# Sheet1.net
KiCad netlist of a schematic drawn in Altium Designer
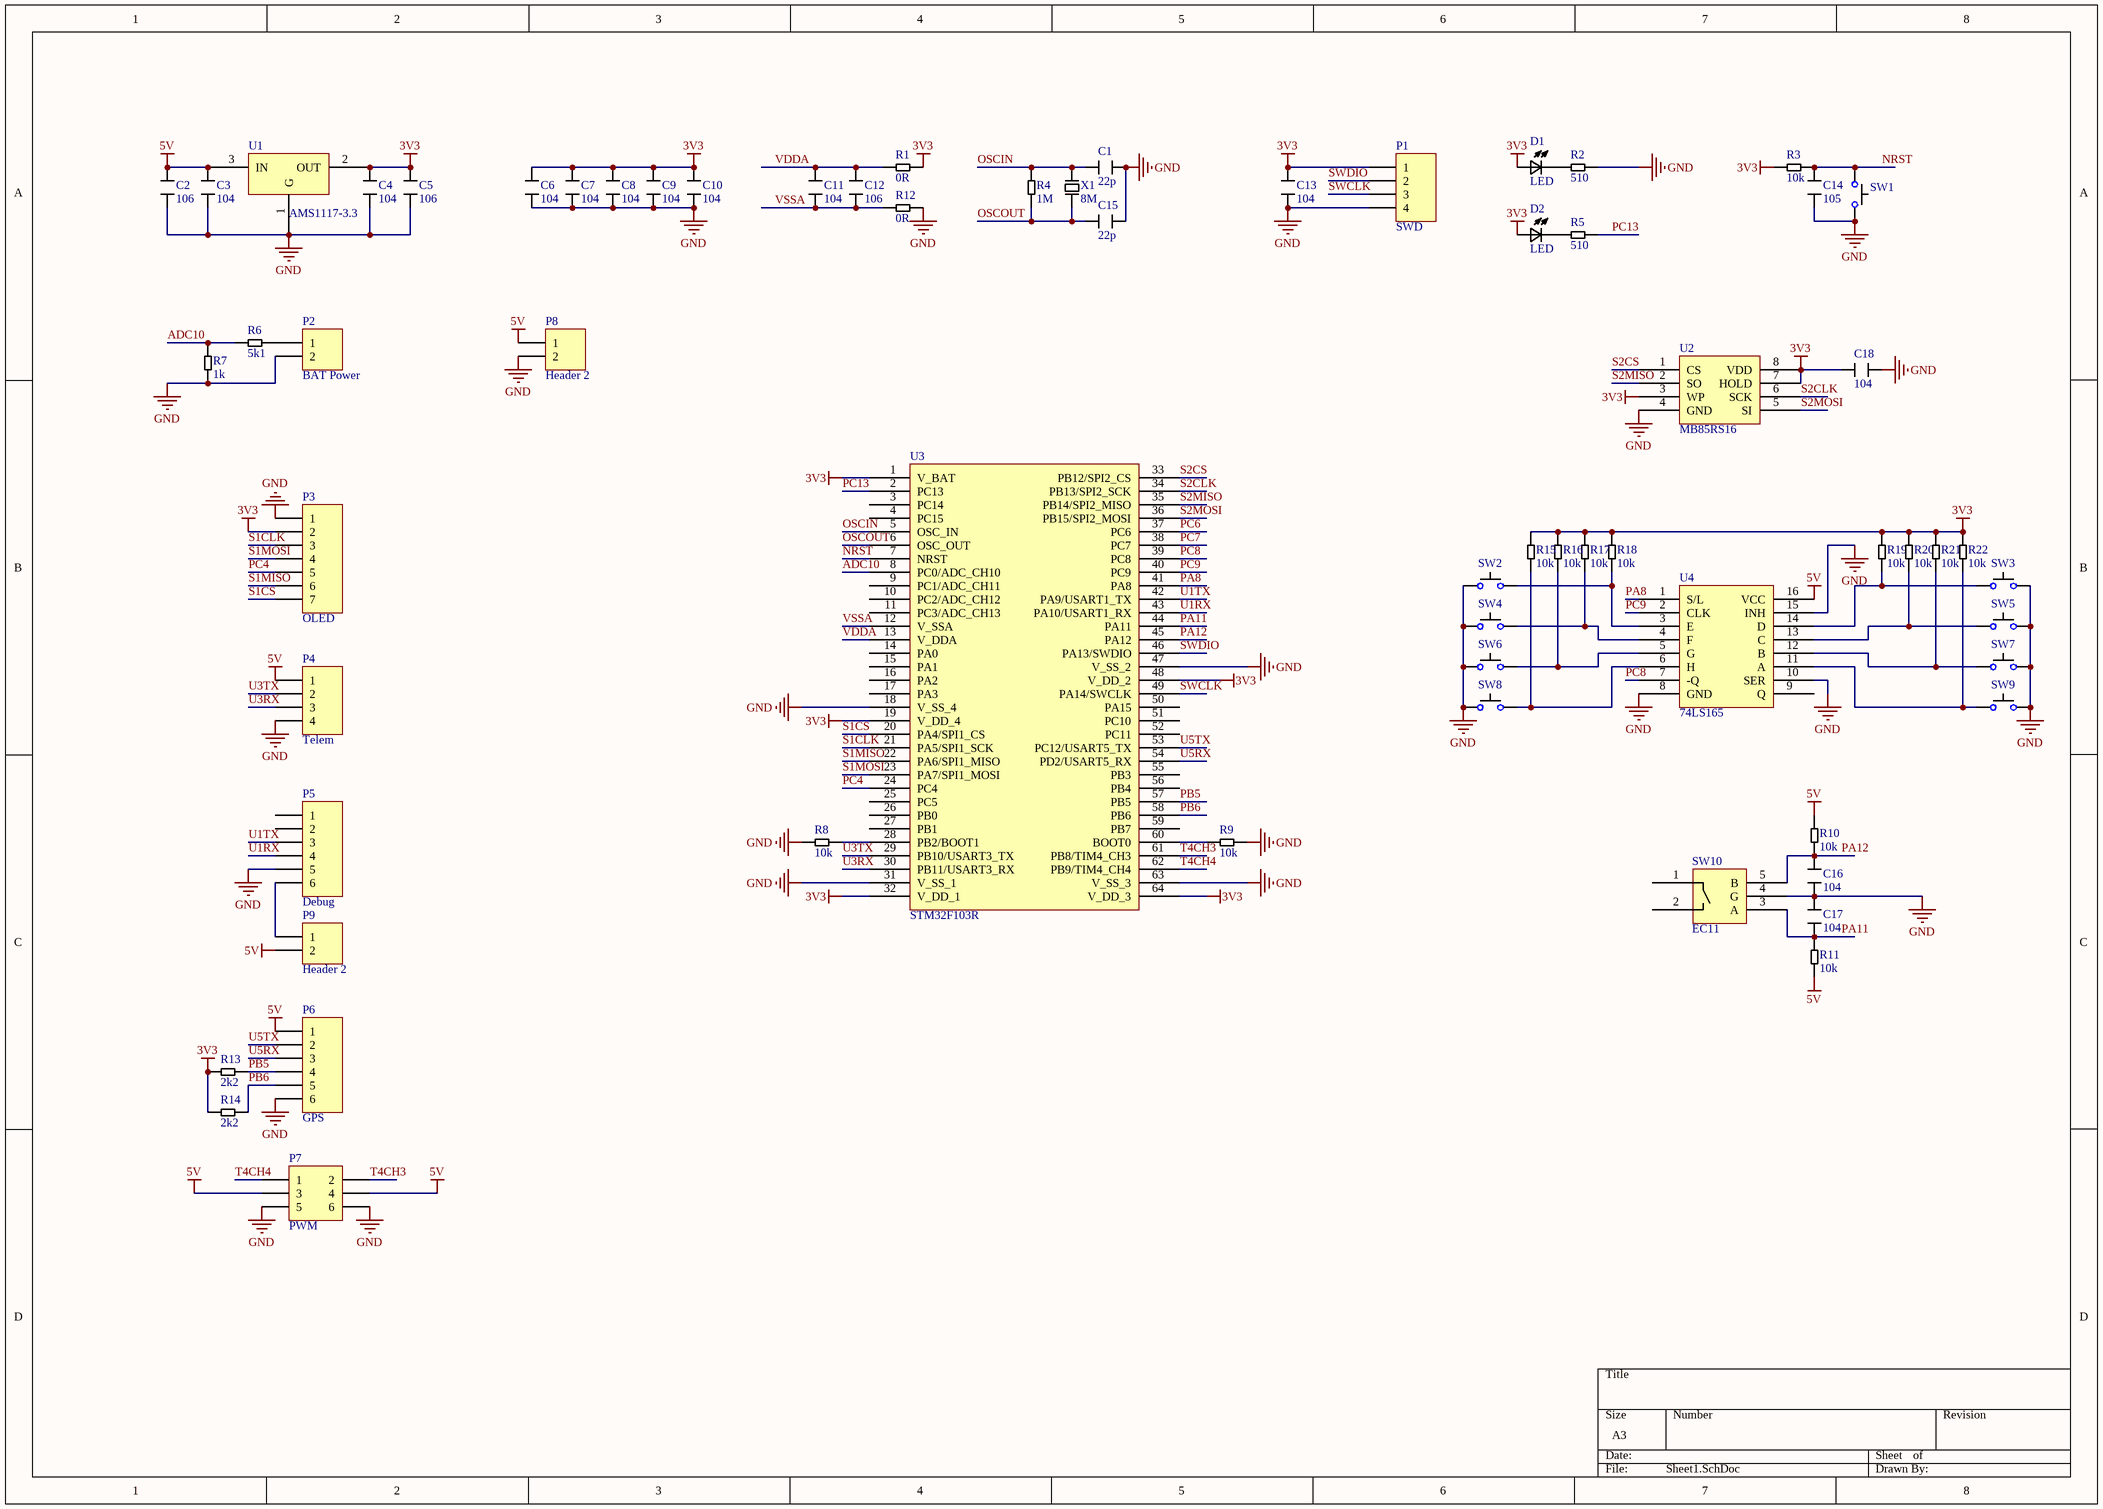
[diagram p0: Sheet1.SchDoc]

(export (version "E")
  (design (tool "Eeschema 10.0.6"))
  (components
    (comp (ref "C1") (value "22p") (footprint "0805") (libsource (lib "Schlib1") (part "Cap")))
    (comp (ref "C2") (value "106") (footprint "0805") (libsource (lib "Schlib1") (part "Cap")))
    (comp (ref "C3") (value "104") (footprint "0805") (libsource (lib "Schlib1") (part "Cap")))
    (comp (ref "C4") (value "104") (footprint "0805") (libsource (lib "Schlib1") (part "Cap")))
    (comp (ref "C5") (value "106") (footprint "0805") (libsource (lib "Schlib1") (part "Cap")))
    (comp (ref "C6") (value "104") (footprint "0805") (libsource (lib "Schlib1") (part "Cap")))
    (comp (ref "C7") (value "104") (footprint "0805") (libsource (lib "Schlib1") (part "Cap")))
    (comp (ref "C8") (value "104") (footprint "0805") (libsource (lib "Schlib1") (part "Cap")))
    (comp (ref "C9") (value "104") (footprint "0805") (libsource (lib "Schlib1") (part "Cap")))
    (comp (ref "C10") (value "104") (footprint "0805") (libsource (lib "Schlib1") (part "Cap")))
    (comp (ref "C11") (value "104") (footprint "0805") (libsource (lib "Schlib1") (part "Cap")))
    (comp (ref "C12") (value "106") (footprint "0805") (libsource (lib "Schlib1") (part "Cap")))
    (comp (ref "C13") (value "104") (footprint "0805") (libsource (lib "Schlib1") (part "Cap")))
    (comp (ref "C14") (value "105") (footprint "0805") (libsource (lib "Schlib1") (part "Cap")))
    (comp (ref "C15") (value "22p") (footprint "0805") (libsource (lib "Schlib1") (part "Cap")))
    (comp (ref "C16") (value "104") (footprint "0805") (libsource (lib "Schlib1") (part "Cap")))
    (comp (ref "C17") (value "104") (footprint "0805") (libsource (lib "Schlib1") (part "Cap")))
    (comp (ref "C18") (value "104") (footprint "0805") (libsource (lib "Schlib1") (part "Cap")))
    (comp (ref "D1") (value "LED") (footprint "0805") (libsource (lib "Schlib1") (part "LED")))
    (comp (ref "D2") (value "LED") (footprint "0805") (libsource (lib "Schlib1") (part "LED")))
    (comp (ref "P1")
      (value "SWD")
      (footprint "HDR1X4")
      (description "Header, 4-Pin")
      (fields (field (name "PUBLISHER") "Altium Limited"))
      (libsource (lib "Miscellaneous Connectors") (part "Header 4"))
    )
    (comp (ref "P2")
      (value "BAT Power")
      (footprint "HDR1X2")
      (description "Header, 2-Pin")
      (fields (field (name "PUBLISHER") "Altium Limited"))
      (libsource (lib "Miscellaneous Connectors") (part "Header 2"))
    )
    (comp (ref "P3")
      (value "OLED")
      (footprint "HDR1X7")
      (description "Header, 7-Pin")
      (fields (field (name "PUBLISHER") "Altium Limited"))
      (libsource (lib "Miscellaneous Connectors") (part "Header 7"))
    )
    (comp (ref "P4")
      (value "Telem")
      (footprint "HDR1X4")
      (description "Header, 4-Pin")
      (fields (field (name "PUBLISHER") "Altium Limited"))
      (libsource (lib "Miscellaneous Connectors") (part "Header 4"))
    )
    (comp (ref "P5")
      (value "Debug")
      (footprint "HDR1X6")
      (description "Header, 6-Pin")
      (fields (field (name "PUBLISHER") "Altium Limited"))
      (libsource (lib "Miscellaneous Connectors") (part "Header 6"))
    )
    (comp (ref "P6")
      (value "GPS")
      (footprint "HDR1X6")
      (description "Header, 6-Pin")
      (fields (field (name "PUBLISHER") "Altium Limited"))
      (libsource (lib "Miscellaneous Connectors") (part "Header 6"))
    )
    (comp (ref "P7")
      (value "PWM")
      (footprint "HDR2X3")
      (description "Header, 3-Pin, Dual row")
      (fields (field (name "PUBLISHER") "Altium Limited"))
      (libsource (lib "Miscellaneous Connectors") (part "Header 3X2"))
    )
    (comp (ref "P8")
      (value "Header 2")
      (footprint "HDR1X2")
      (description "Header, 2-Pin")
      (fields (field (name "PUBLISHER") "Altium Limited"))
      (libsource (lib "Miscellaneous Connectors") (part "Header 2"))
    )
    (comp (ref "P9")
      (value "Header 2")
      (footprint "HDR1X2")
      (description "Header, 2-Pin")
      (fields (field (name "PUBLISHER") "Altium Limited"))
      (libsource (lib "Miscellaneous Connectors") (part "Header 2"))
    )
    (comp (ref "R1") (value "0R") (footprint "0805") (libsource (lib "Schlib1") (part "Res")))
    (comp (ref "R2") (value "510") (footprint "0805") (libsource (lib "Schlib1") (part "Res")))
    (comp (ref "R3") (value "10k") (footprint "0805") (libsource (lib "Schlib1") (part "Res")))
    (comp (ref "R4") (value "1M") (footprint "0805") (libsource (lib "Schlib1") (part "Res")))
    (comp (ref "R5") (value "510") (footprint "0805") (libsource (lib "Schlib1") (part "Res")))
    (comp (ref "R6") (value "5k1") (footprint "0805") (libsource (lib "Schlib1") (part "Res")))
    (comp (ref "R7") (value "1k") (footprint "0805") (libsource (lib "Schlib1") (part "Res")))
    (comp (ref "R8") (value "10k") (footprint "0805") (libsource (lib "Schlib1") (part "Res")))
    (comp (ref "R9") (value "10k") (footprint "0805") (libsource (lib "Schlib1") (part "Res")))
    (comp (ref "R10") (value "10k") (footprint "0805") (libsource (lib "Schlib1") (part "Res")))
    (comp (ref "R11") (value "10k") (footprint "0805") (libsource (lib "Schlib1") (part "Res")))
    (comp (ref "R12") (value "0R") (footprint "0805") (libsource (lib "Schlib1") (part "Res")))
    (comp (ref "R13") (value "2k2") (footprint "0805") (libsource (lib "Schlib1") (part "Res")))
    (comp (ref "R14") (value "2k2") (footprint "0805") (libsource (lib "Schlib1") (part "Res")))
    (comp (ref "R15") (value "10k") (footprint "0805") (libsource (lib "Schlib1") (part "Res")))
    (comp (ref "R16") (value "10k") (footprint "0805") (libsource (lib "Schlib1") (part "Res")))
    (comp (ref "R17") (value "10k") (footprint "0805") (libsource (lib "Schlib1") (part "Res")))
    (comp (ref "R18") (value "10k") (footprint "0805") (libsource (lib "Schlib1") (part "Res")))
    (comp (ref "R19") (value "10k") (footprint "0805") (libsource (lib "Schlib1") (part "Res")))
    (comp (ref "R20") (value "10k") (footprint "0805") (libsource (lib "Schlib1") (part "Res")))
    (comp (ref "R21") (value "10k") (footprint "0805") (libsource (lib "Schlib1") (part "Res")))
    (comp (ref "R22") (value "10k") (footprint "0805") (libsource (lib "Schlib1") (part "Res")))
    (comp (ref "SW1") (value "~") (footprint "Btn") (libsource (lib "Schlib1") (part "Btn")))
    (comp (ref "SW2") (value "~") (footprint "Btn") (libsource (lib "Schlib1") (part "Btn")))
    (comp (ref "SW3") (value "~") (footprint "Btn") (libsource (lib "Schlib1") (part "Btn")))
    (comp (ref "SW4") (value "~") (footprint "Btn") (libsource (lib "Schlib1") (part "Btn")))
    (comp (ref "SW5") (value "~") (footprint "Btn") (libsource (lib "Schlib1") (part "Btn")))
    (comp (ref "SW6") (value "~") (footprint "Btn") (libsource (lib "Schlib1") (part "Btn")))
    (comp (ref "SW7") (value "~") (footprint "Btn") (libsource (lib "Schlib1") (part "Btn")))
    (comp (ref "SW8") (value "~") (footprint "Btn") (libsource (lib "Schlib1") (part "Btn")))
    (comp (ref "SW9") (value "~") (footprint "Btn") (libsource (lib "Schlib1") (part "Btn")))
    (comp (ref "SW10") (value "EC11") (footprint "EC11") (libsource (lib "Schlib1") (part "EC11")))
    (comp (ref "U1")
      (value "AMS1117-3.3")
      (footprint "SOT223")
      (libsource (lib "Schlib1") (part "AMS1117-3.3"))
    )
    (comp (ref "U2") (value "MB85RS16") (footprint "SOP8") (libsource (lib "Schlib1") (part "MB85RS16")))
    (comp (ref "U3")
      (value "STM32F103R")
      (footprint "LQFP64-M")
      (libsource (lib "Schlib1") (part "STM32F103R"))
    )
    (comp (ref "U4") (value "74LS165") (footprint "SOP16") (libsource (lib "Schlib1") (part "74LS165")))
    (comp (ref "X1") (value "8M") (footprint "49SMD") (libsource (lib "Schlib1") (part "XTAL")))
  )
  (nets
    (net (code "1") (name "/ADC10") (class "Default")
      (node (ref "R6") (pin "1") (pintype "passive"))
      (node (ref "R7") (pin "2") (pintype "passive"))
      (node (ref "U3") (pin "8") (pinfunction "PC0/ADC_CH10_8") (pintype "passive"))
    )
    (net (code "2") (name "/NRST") (class "Default")
      (node (ref "C14") (pin "2") (pintype "passive"))
      (node (ref "R3") (pin "2") (pintype "passive"))
      (node (ref "SW1") (pin "1") (pintype "passive"))
      (node (ref "U3") (pin "7") (pinfunction "NRST_7") (pintype "passive"))
    )
    (net (code "3") (name "/OSCIN") (class "Default")
      (node (ref "C1") (pin "1") (pintype "passive"))
      (node (ref "R4") (pin "2") (pintype "passive"))
      (node (ref "U3") (pin "5") (pinfunction "OSC_IN_5") (pintype "passive"))
      (node (ref "X1") (pin "2") (pintype "passive"))
    )
    (net (code "4") (name "/OSCOUT") (class "Default")
      (node (ref "C15") (pin "1") (pintype "passive"))
      (node (ref "R4") (pin "1") (pintype "passive"))
      (node (ref "U3") (pin "6") (pinfunction "OSC_OUT_6") (pintype "passive"))
      (node (ref "X1") (pin "1") (pintype "passive"))
    )
    (net (code "5") (name "/PA8") (class "Default")
      (node (ref "U3") (pin "41") (pinfunction "PA8_41") (pintype "passive"))
      (node (ref "U4") (pin "1") (pinfunction "S/L_1") (pintype "passive"))
    )
    (net (code "6") (name "/PA11") (class "Default")
      (node (ref "C17") (pin "1") (pintype "passive"))
      (node (ref "R11") (pin "2") (pintype "passive"))
      (node (ref "SW10") (pin "3") (pinfunction "A_3") (pintype "passive"))
      (node (ref "U3") (pin "44") (pinfunction "PA11_44") (pintype "passive"))
    )
    (net (code "7") (name "/PA12") (class "Default")
      (node (ref "C16") (pin "2") (pintype "passive"))
      (node (ref "R10") (pin "1") (pintype "passive"))
      (node (ref "SW10") (pin "5") (pinfunction "B_5") (pintype "passive"))
      (node (ref "U3") (pin "45") (pinfunction "PA12_45") (pintype "passive"))
    )
    (net (code "8") (name "/PB5") (class "Default")
      (node (ref "P6") (pin "4") (pinfunction "4_4") (pintype "passive"))
      (node (ref "R13") (pin "2") (pintype "passive"))
      (node (ref "U3") (pin "57") (pinfunction "PB5_57") (pintype "passive"))
    )
    (net (code "9") (name "/PB6") (class "Default")
      (node (ref "P6") (pin "5") (pinfunction "5_5") (pintype "passive"))
      (node (ref "R14") (pin "2") (pintype "passive"))
      (node (ref "U3") (pin "58") (pinfunction "PB6_58") (pintype "passive"))
    )
    (net (code "10") (name "/PC4") (class "Default")
      (node (ref "P3") (pin "5") (pinfunction "5_5") (pintype "passive"))
      (node (ref "U3") (pin "24") (pinfunction "PC4_24") (pintype "passive"))
    )
    (net (code "11") (name "/PC6") (class "Default")
      (node (ref "U3") (pin "37") (pinfunction "PC6_37") (pintype "passive"))
    )
    (net (code "12") (name "/PC7") (class "Default")
      (node (ref "U3") (pin "38") (pinfunction "PC7_38") (pintype "passive"))
    )
    (net (code "13") (name "/PC8") (class "Default")
      (node (ref "U3") (pin "39") (pinfunction "PC8_39") (pintype "passive"))
      (node (ref "U4") (pin "7") (pinfunction "-Q_7") (pintype "passive"))
    )
    (net (code "14") (name "/PC9") (class "Default")
      (node (ref "U3") (pin "40") (pinfunction "PC9_40") (pintype "passive"))
      (node (ref "U4") (pin "2") (pinfunction "CLK_2") (pintype "passive"))
    )
    (net (code "15") (name "/PC13") (class "Default")
      (node (ref "R5") (pin "2") (pintype "passive"))
      (node (ref "U3") (pin "2") (pinfunction "PC13_2") (pintype "passive"))
    )
    (net (code "16") (name "/S1CLK") (class "Default")
      (node (ref "P3") (pin "3") (pinfunction "3_3") (pintype "passive"))
      (node (ref "U3") (pin "21") (pinfunction "PA5/SPI1_SCK_21") (pintype "passive"))
    )
    (net (code "17") (name "/S1CS") (class "Default")
      (node (ref "P3") (pin "7") (pinfunction "7_7") (pintype "passive"))
      (node (ref "U3") (pin "20") (pinfunction "PA4/SPI1_CS_20") (pintype "passive"))
    )
    (net (code "18") (name "/S1MISO") (class "Default")
      (node (ref "P3") (pin "6") (pinfunction "6_6") (pintype "passive"))
      (node (ref "U3") (pin "22") (pinfunction "PA6/SPI1_MISO_22") (pintype "passive"))
    )
    (net (code "19") (name "/S1MOSI") (class "Default")
      (node (ref "P3") (pin "4") (pinfunction "4_4") (pintype "passive"))
      (node (ref "U3") (pin "23") (pinfunction "PA7/SPI1_MOSI_23") (pintype "passive"))
    )
    (net (code "20") (name "/S2CLK") (class "Default")
      (node (ref "U2") (pin "6") (pinfunction "SCK_6") (pintype "passive"))
      (node (ref "U3") (pin "34") (pinfunction "PB13/SPI2_SCK_34") (pintype "passive"))
    )
    (net (code "21") (name "/S2CS") (class "Default")
      (node (ref "U2") (pin "1") (pinfunction "CS_1") (pintype "passive"))
      (node (ref "U3") (pin "33") (pinfunction "PB12/SPI2_CS_33") (pintype "passive"))
    )
    (net (code "22") (name "/S2MISO") (class "Default")
      (node (ref "U2") (pin "2") (pinfunction "SO_2") (pintype "passive"))
      (node (ref "U3") (pin "35") (pinfunction "PB14/SPI2_MISO_35") (pintype "passive"))
    )
    (net (code "23") (name "/S2MOSI") (class "Default")
      (node (ref "U2") (pin "5") (pinfunction "SI_5") (pintype "passive"))
      (node (ref "U3") (pin "36") (pinfunction "PB15/SPI2_MOSI_36") (pintype "passive"))
    )
    (net (code "24") (name "/SWCLK") (class "Default")
      (node (ref "P1") (pin "3") (pinfunction "3_3") (pintype "passive"))
      (node (ref "U3") (pin "49") (pinfunction "PA14/SWCLK_49") (pintype "passive"))
    )
    (net (code "25") (name "/SWDIO") (class "Default")
      (node (ref "P1") (pin "2") (pinfunction "2_2") (pintype "passive"))
      (node (ref "U3") (pin "46") (pinfunction "PA13/SWDIO_46") (pintype "passive"))
    )
    (net (code "26") (name "/T4CH3") (class "Default")
      (node (ref "P7") (pin "2") (pinfunction "2_2") (pintype "passive"))
      (node (ref "U3") (pin "61") (pinfunction "PB8/TIM4_CH3_61") (pintype "passive"))
    )
    (net (code "27") (name "/T4CH4") (class "Default")
      (node (ref "P7") (pin "1") (pinfunction "1_1") (pintype "passive"))
      (node (ref "U3") (pin "62") (pinfunction "PB9/TIM4_CH4_62") (pintype "passive"))
    )
    (net (code "28") (name "/U1RX") (class "Default")
      (node (ref "P5") (pin "4") (pinfunction "4_4") (pintype "passive"))
      (node (ref "U3") (pin "43") (pinfunction "PA10/USART1_RX_43") (pintype "passive"))
    )
    (net (code "29") (name "/U1TX") (class "Default")
      (node (ref "P5") (pin "3") (pinfunction "3_3") (pintype "passive"))
      (node (ref "U3") (pin "42") (pinfunction "PA9/USART1_TX_42") (pintype "passive"))
    )
    (net (code "30") (name "/U3RX") (class "Default")
      (node (ref "P4") (pin "3") (pinfunction "3_3") (pintype "passive"))
      (node (ref "U3") (pin "30") (pinfunction "PB11/USART3_RX_30") (pintype "passive"))
    )
    (net (code "31") (name "/U3TX") (class "Default")
      (node (ref "P4") (pin "2") (pinfunction "2_2") (pintype "passive"))
      (node (ref "U3") (pin "29") (pinfunction "PB10/USART3_TX_29") (pintype "passive"))
    )
    (net (code "32") (name "/U5RX") (class "Default")
      (node (ref "P6") (pin "3") (pinfunction "3_3") (pintype "passive"))
      (node (ref "U3") (pin "54") (pinfunction "PD2/USART5_RX_54") (pintype "passive"))
    )
    (net (code "33") (name "/U5TX") (class "Default")
      (node (ref "P6") (pin "2") (pinfunction "2_2") (pintype "passive"))
      (node (ref "U3") (pin "53") (pinfunction "PC12/USART5_TX_53") (pintype "passive"))
    )
    (net (code "34") (name "/VDDA") (class "Default")
      (node (ref "C11") (pin "2") (pintype "passive"))
      (node (ref "C12") (pin "2") (pintype "passive"))
      (node (ref "R1") (pin "1") (pintype "passive"))
      (node (ref "U3") (pin "13") (pinfunction "V_DDA_13") (pintype "passive"))
    )
    (net (code "35") (name "/VSSA") (class "Default")
      (node (ref "C11") (pin "1") (pintype "passive"))
      (node (ref "C12") (pin "1") (pintype "passive"))
      (node (ref "R12") (pin "1") (pintype "passive"))
      (node (ref "U3") (pin "12") (pinfunction "V_SSA_12") (pintype "passive"))
    )
    (net (code "36") (name "3V3") (class "Default")
      (node (ref "C10") (pin "2") (pintype "passive"))
      (node (ref "C13") (pin "2") (pintype "passive"))
      (node (ref "C18") (pin "1") (pintype "passive"))
      (node (ref "C4") (pin "2") (pintype "passive"))
      (node (ref "C5") (pin "2") (pintype "passive"))
      (node (ref "C6") (pin "2") (pintype "passive"))
      (node (ref "C7") (pin "2") (pintype "passive"))
      (node (ref "C8") (pin "2") (pintype "passive"))
      (node (ref "C9") (pin "2") (pintype "passive"))
      (node (ref "D1") (pin "1") (pintype "passive"))
      (node (ref "D2") (pin "1") (pintype "passive"))
      (node (ref "P1") (pin "1") (pinfunction "1_1") (pintype "passive"))
      (node (ref "P3") (pin "2") (pinfunction "2_2") (pintype "passive"))
      (node (ref "R1") (pin "2") (pintype "passive"))
      (node (ref "R13") (pin "1") (pintype "passive"))
      (node (ref "R14") (pin "1") (pintype "passive"))
      (node (ref "R15") (pin "2") (pintype "passive"))
      (node (ref "R16") (pin "2") (pintype "passive"))
      (node (ref "R17") (pin "2") (pintype "passive"))
      (node (ref "R18") (pin "2") (pintype "passive"))
      (node (ref "R19") (pin "2") (pintype "passive"))
      (node (ref "R20") (pin "2") (pintype "passive"))
      (node (ref "R21") (pin "2") (pintype "passive"))
      (node (ref "R22") (pin "2") (pintype "passive"))
      (node (ref "R3") (pin "1") (pintype "passive"))
      (node (ref "U1") (pin "2") (pinfunction "OUT_2") (pintype "passive"))
      (node (ref "U2") (pin "3") (pinfunction "WP_3") (pintype "passive"))
      (node (ref "U2") (pin "7") (pinfunction "HOLD_7") (pintype "passive"))
      (node (ref "U2") (pin "8") (pinfunction "VDD_8") (pintype "passive"))
      (node (ref "U3") (pin "1") (pinfunction "V_BAT_1") (pintype "passive"))
      (node (ref "U3") (pin "19") (pinfunction "V_DD_4_19") (pintype "passive"))
      (node (ref "U3") (pin "32") (pinfunction "V_DD_1_32") (pintype "passive"))
      (node (ref "U3") (pin "48") (pinfunction "V_DD_2_48") (pintype "passive"))
      (node (ref "U3") (pin "64") (pinfunction "V_DD_3_64") (pintype "passive"))
    )
    (net (code "37") (name "5V") (class "Default")
      (node (ref "C2") (pin "2") (pintype "passive"))
      (node (ref "C3") (pin "2") (pintype "passive"))
      (node (ref "P4") (pin "1") (pinfunction "1_1") (pintype "passive"))
      (node (ref "P6") (pin "1") (pinfunction "1_1") (pintype "passive"))
      (node (ref "P7") (pin "3") (pinfunction "3_3") (pintype "passive"))
      (node (ref "P7") (pin "4") (pinfunction "4_4") (pintype "passive"))
      (node (ref "P8") (pin "1") (pinfunction "1_1") (pintype "passive"))
      (node (ref "P9") (pin "2") (pinfunction "2_2") (pintype "passive"))
      (node (ref "R10") (pin "2") (pintype "passive"))
      (node (ref "R11") (pin "1") (pintype "passive"))
      (node (ref "U1") (pin "3") (pinfunction "IN_3") (pintype "passive"))
      (node (ref "U4") (pin "16") (pinfunction "VCC_16") (pintype "passive"))
    )
    (net (code "38") (name "GND") (class "Default")
      (node (ref "C1") (pin "2") (pintype "passive"))
      (node (ref "C10") (pin "1") (pintype "passive"))
      (node (ref "C13") (pin "1") (pintype "passive"))
      (node (ref "C14") (pin "1") (pintype "passive"))
      (node (ref "C15") (pin "2") (pintype "passive"))
      (node (ref "C16") (pin "1") (pintype "passive"))
      (node (ref "C17") (pin "2") (pintype "passive"))
      (node (ref "C18") (pin "2") (pintype "passive"))
      (node (ref "C2") (pin "1") (pintype "passive"))
      (node (ref "C3") (pin "1") (pintype "passive"))
      (node (ref "C4") (pin "1") (pintype "passive"))
      (node (ref "C5") (pin "1") (pintype "passive"))
      (node (ref "C6") (pin "1") (pintype "passive"))
      (node (ref "C7") (pin "1") (pintype "passive"))
      (node (ref "C8") (pin "1") (pintype "passive"))
      (node (ref "C9") (pin "1") (pintype "passive"))
      (node (ref "P1") (pin "4") (pinfunction "4_4") (pintype "passive"))
      (node (ref "P2") (pin "2") (pinfunction "2_2") (pintype "passive"))
      (node (ref "P3") (pin "1") (pinfunction "1_1") (pintype "passive"))
      (node (ref "P4") (pin "4") (pinfunction "4_4") (pintype "passive"))
      (node (ref "P5") (pin "5") (pinfunction "5_5") (pintype "passive"))
      (node (ref "P6") (pin "6") (pinfunction "6_6") (pintype "passive"))
      (node (ref "P7") (pin "5") (pinfunction "5_5") (pintype "passive"))
      (node (ref "P7") (pin "6") (pinfunction "6_6") (pintype "passive"))
      (node (ref "P8") (pin "2") (pinfunction "2_2") (pintype "passive"))
      (node (ref "R12") (pin "2") (pintype "passive"))
      (node (ref "R2") (pin "2") (pintype "passive"))
      (node (ref "R7") (pin "1") (pintype "passive"))
      (node (ref "R8") (pin "1") (pintype "passive"))
      (node (ref "R9") (pin "2") (pintype "passive"))
      (node (ref "SW1") (pin "2") (pintype "passive"))
      (node (ref "SW10") (pin "4") (pinfunction "G_4") (pintype "passive"))
      (node (ref "SW2") (pin "1") (pintype "passive"))
      (node (ref "SW3") (pin "2") (pintype "passive"))
      (node (ref "SW4") (pin "1") (pintype "passive"))
      (node (ref "SW5") (pin "2") (pintype "passive"))
      (node (ref "SW6") (pin "1") (pintype "passive"))
      (node (ref "SW7") (pin "2") (pintype "passive"))
      (node (ref "SW8") (pin "1") (pintype "passive"))
      (node (ref "SW9") (pin "2") (pintype "passive"))
      (node (ref "U1") (pin "1") (pinfunction "G_1") (pintype "passive"))
      (node (ref "U2") (pin "4") (pinfunction "GND_4") (pintype "passive"))
      (node (ref "U3") (pin "18") (pinfunction "V_SS_4_18") (pintype "passive"))
      (node (ref "U3") (pin "31") (pinfunction "V_SS_1_31") (pintype "passive"))
      (node (ref "U3") (pin "47") (pinfunction "V_SS_2_47") (pintype "passive"))
      (node (ref "U3") (pin "63") (pinfunction "V_SS_3_63") (pintype "passive"))
      (node (ref "U4") (pin "10") (pinfunction "SER_10") (pintype "passive"))
      (node (ref "U4") (pin "15") (pinfunction "INH_15") (pintype "passive"))
      (node (ref "U4") (pin "8") (pinfunction "GND_8") (pintype "passive"))
    )
    (net (code "39") (name "Net-(D1-Pad2)") (class "Default")
      (node (ref "D1") (pin "2") (pintype "passive"))
      (node (ref "R2") (pin "1") (pintype "passive"))
    )
    (net (code "40") (name "Net-(D2-Pad2)") (class "Default")
      (node (ref "D2") (pin "2") (pintype "passive"))
      (node (ref "R5") (pin "1") (pintype "passive"))
    )
    (net (code "41") (name "Net-(P2-Pad1)") (class "Default")
      (node (ref "P2") (pin "1") (pinfunction "1_1") (pintype "passive"))
      (node (ref "R6") (pin "2") (pintype "passive"))
    )
    (net (code "42") (name "Net-(P5-Pad6)") (class "Default")
      (node (ref "P5") (pin "6") (pinfunction "6_6") (pintype "passive"))
      (node (ref "P9") (pin "1") (pinfunction "1_1") (pintype "passive"))
    )
    (net (code "43") (name "Net-(U3-BOOT0)") (class "Default")
      (node (ref "R9") (pin "1") (pintype "passive"))
      (node (ref "U3") (pin "60") (pinfunction "BOOT0_60") (pintype "passive"))
    )
    (net (code "44") (name "Net-(U3-PB2{slash}BOOT1)") (class "Default")
      (node (ref "R8") (pin "2") (pintype "passive"))
      (node (ref "U3") (pin "28") (pinfunction "PB2/BOOT1_28") (pintype "passive"))
    )
    (net (code "45") (name "Net-(U4-A)") (class "Default")
      (node (ref "R22") (pin "1") (pintype "passive"))
      (node (ref "SW9") (pin "1") (pintype "passive"))
      (node (ref "U4") (pin "11") (pinfunction "A_11") (pintype "passive"))
    )
    (net (code "46") (name "Net-(U4-B)") (class "Default")
      (node (ref "R21") (pin "1") (pintype "passive"))
      (node (ref "SW7") (pin "1") (pintype "passive"))
      (node (ref "U4") (pin "12") (pinfunction "B_12") (pintype "passive"))
    )
    (net (code "47") (name "Net-(U4-C)") (class "Default")
      (node (ref "R20") (pin "1") (pintype "passive"))
      (node (ref "SW5") (pin "1") (pintype "passive"))
      (node (ref "U4") (pin "13") (pinfunction "C_13") (pintype "passive"))
    )
    (net (code "48") (name "Net-(U4-D)") (class "Default")
      (node (ref "R19") (pin "1") (pintype "passive"))
      (node (ref "SW3") (pin "1") (pintype "passive"))
      (node (ref "U4") (pin "14") (pinfunction "D_14") (pintype "passive"))
    )
    (net (code "49") (name "Net-(U4-E)") (class "Default")
      (node (ref "R18") (pin "1") (pintype "passive"))
      (node (ref "SW2") (pin "2") (pintype "passive"))
      (node (ref "U4") (pin "3") (pinfunction "E_3") (pintype "passive"))
    )
    (net (code "50") (name "Net-(U4-F)") (class "Default")
      (node (ref "R17") (pin "1") (pintype "passive"))
      (node (ref "SW4") (pin "2") (pintype "passive"))
      (node (ref "U4") (pin "4") (pinfunction "F_4") (pintype "passive"))
    )
    (net (code "51") (name "Net-(U4-G)") (class "Default")
      (node (ref "R16") (pin "1") (pintype "passive"))
      (node (ref "SW6") (pin "2") (pintype "passive"))
      (node (ref "U4") (pin "5") (pinfunction "G_5") (pintype "passive"))
    )
    (net (code "52") (name "Net-(U4-H)") (class "Default")
      (node (ref "R15") (pin "1") (pintype "passive"))
      (node (ref "SW8") (pin "2") (pintype "passive"))
      (node (ref "U4") (pin "6") (pinfunction "H_6") (pintype "passive"))
    )
    (net (code "53") (name "unconnected-(P5-Pad1)") (class "Default")
      (node (ref "P5") (pin "1") (pinfunction "1_1") (pintype "passive"))
    )
    (net (code "54") (name "unconnected-(P5-Pad2)") (class "Default")
      (node (ref "P5") (pin "2") (pinfunction "2_2") (pintype "passive"))
    )
    (net (code "55") (name "unconnected-(SW10-A-Pad2)") (class "Default")
      (node (ref "SW10") (pin "2") (pinfunction "A_2") (pintype "passive"))
    )
    (net (code "56") (name "unconnected-(SW10-K-Pad1)") (class "Default")
      (node (ref "SW10") (pin "1") (pinfunction "K_1") (pintype "passive"))
    )
    (net (code "57") (name "unconnected-(U3-PA0-Pad14)") (class "Default")
      (node (ref "U3") (pin "14") (pinfunction "PA0_14") (pintype "passive"))
    )
    (net (code "58") (name "unconnected-(U3-PA1-Pad15)") (class "Default")
      (node (ref "U3") (pin "15") (pinfunction "PA1_15") (pintype "passive"))
    )
    (net (code "59") (name "unconnected-(U3-PA2-Pad16)") (class "Default")
      (node (ref "U3") (pin "16") (pinfunction "PA2_16") (pintype "passive"))
    )
    (net (code "60") (name "unconnected-(U3-PA3-Pad17)") (class "Default")
      (node (ref "U3") (pin "17") (pinfunction "PA3_17") (pintype "passive"))
    )
    (net (code "61") (name "unconnected-(U3-PA15-Pad50)") (class "Default")
      (node (ref "U3") (pin "50") (pinfunction "PA15_50") (pintype "passive"))
    )
    (net (code "62") (name "unconnected-(U3-PB0-Pad26)") (class "Default")
      (node (ref "U3") (pin "26") (pinfunction "PB0_26") (pintype "passive"))
    )
    (net (code "63") (name "unconnected-(U3-PB1-Pad27)") (class "Default")
      (node (ref "U3") (pin "27") (pinfunction "PB1_27") (pintype "passive"))
    )
    (net (code "64") (name "unconnected-(U3-PB3-Pad55)") (class "Default")
      (node (ref "U3") (pin "55") (pinfunction "PB3_55") (pintype "passive"))
    )
    (net (code "65") (name "unconnected-(U3-PB4-Pad56)") (class "Default")
      (node (ref "U3") (pin "56") (pinfunction "PB4_56") (pintype "passive"))
    )
    (net (code "66") (name "unconnected-(U3-PB7-Pad59)") (class "Default")
      (node (ref "U3") (pin "59") (pinfunction "PB7_59") (pintype "passive"))
    )
    (net (code "67") (name "unconnected-(U3-PC1{slash}ADC_CH11-Pad9)") (class "Default")
      (node (ref "U3") (pin "9") (pinfunction "PC1/ADC_CH11_9") (pintype "passive"))
    )
    (net (code "68") (name "unconnected-(U3-PC2{slash}ADC_CH12-Pad10)") (class "Default")
      (node (ref "U3") (pin "10") (pinfunction "PC2/ADC_CH12_10") (pintype "passive"))
    )
    (net (code "69") (name "unconnected-(U3-PC3{slash}ADC_CH13-Pad11)") (class "Default")
      (node (ref "U3") (pin "11") (pinfunction "PC3/ADC_CH13_11") (pintype "passive"))
    )
    (net (code "70") (name "unconnected-(U3-PC5-Pad25)") (class "Default")
      (node (ref "U3") (pin "25") (pinfunction "PC5_25") (pintype "passive"))
    )
    (net (code "71") (name "unconnected-(U3-PC10-Pad51)") (class "Default")
      (node (ref "U3") (pin "51") (pinfunction "PC10_51") (pintype "passive"))
    )
    (net (code "72") (name "unconnected-(U3-PC11-Pad52)") (class "Default")
      (node (ref "U3") (pin "52") (pinfunction "PC11_52") (pintype "passive"))
    )
    (net (code "73") (name "unconnected-(U3-PC14-Pad3)") (class "Default")
      (node (ref "U3") (pin "3") (pinfunction "PC14_3") (pintype "passive"))
    )
    (net (code "74") (name "unconnected-(U3-PC15-Pad4)") (class "Default")
      (node (ref "U3") (pin "4") (pinfunction "PC15_4") (pintype "passive"))
    )
    (net (code "75") (name "unconnected-(U4-Q-Pad9)") (class "Default")
      (node (ref "U4") (pin "9") (pinfunction "Q_9") (pintype "passive"))
    )
  )
)
